# OBCv5_0.net
KiCad netlist of a schematic drawn in EAGLE
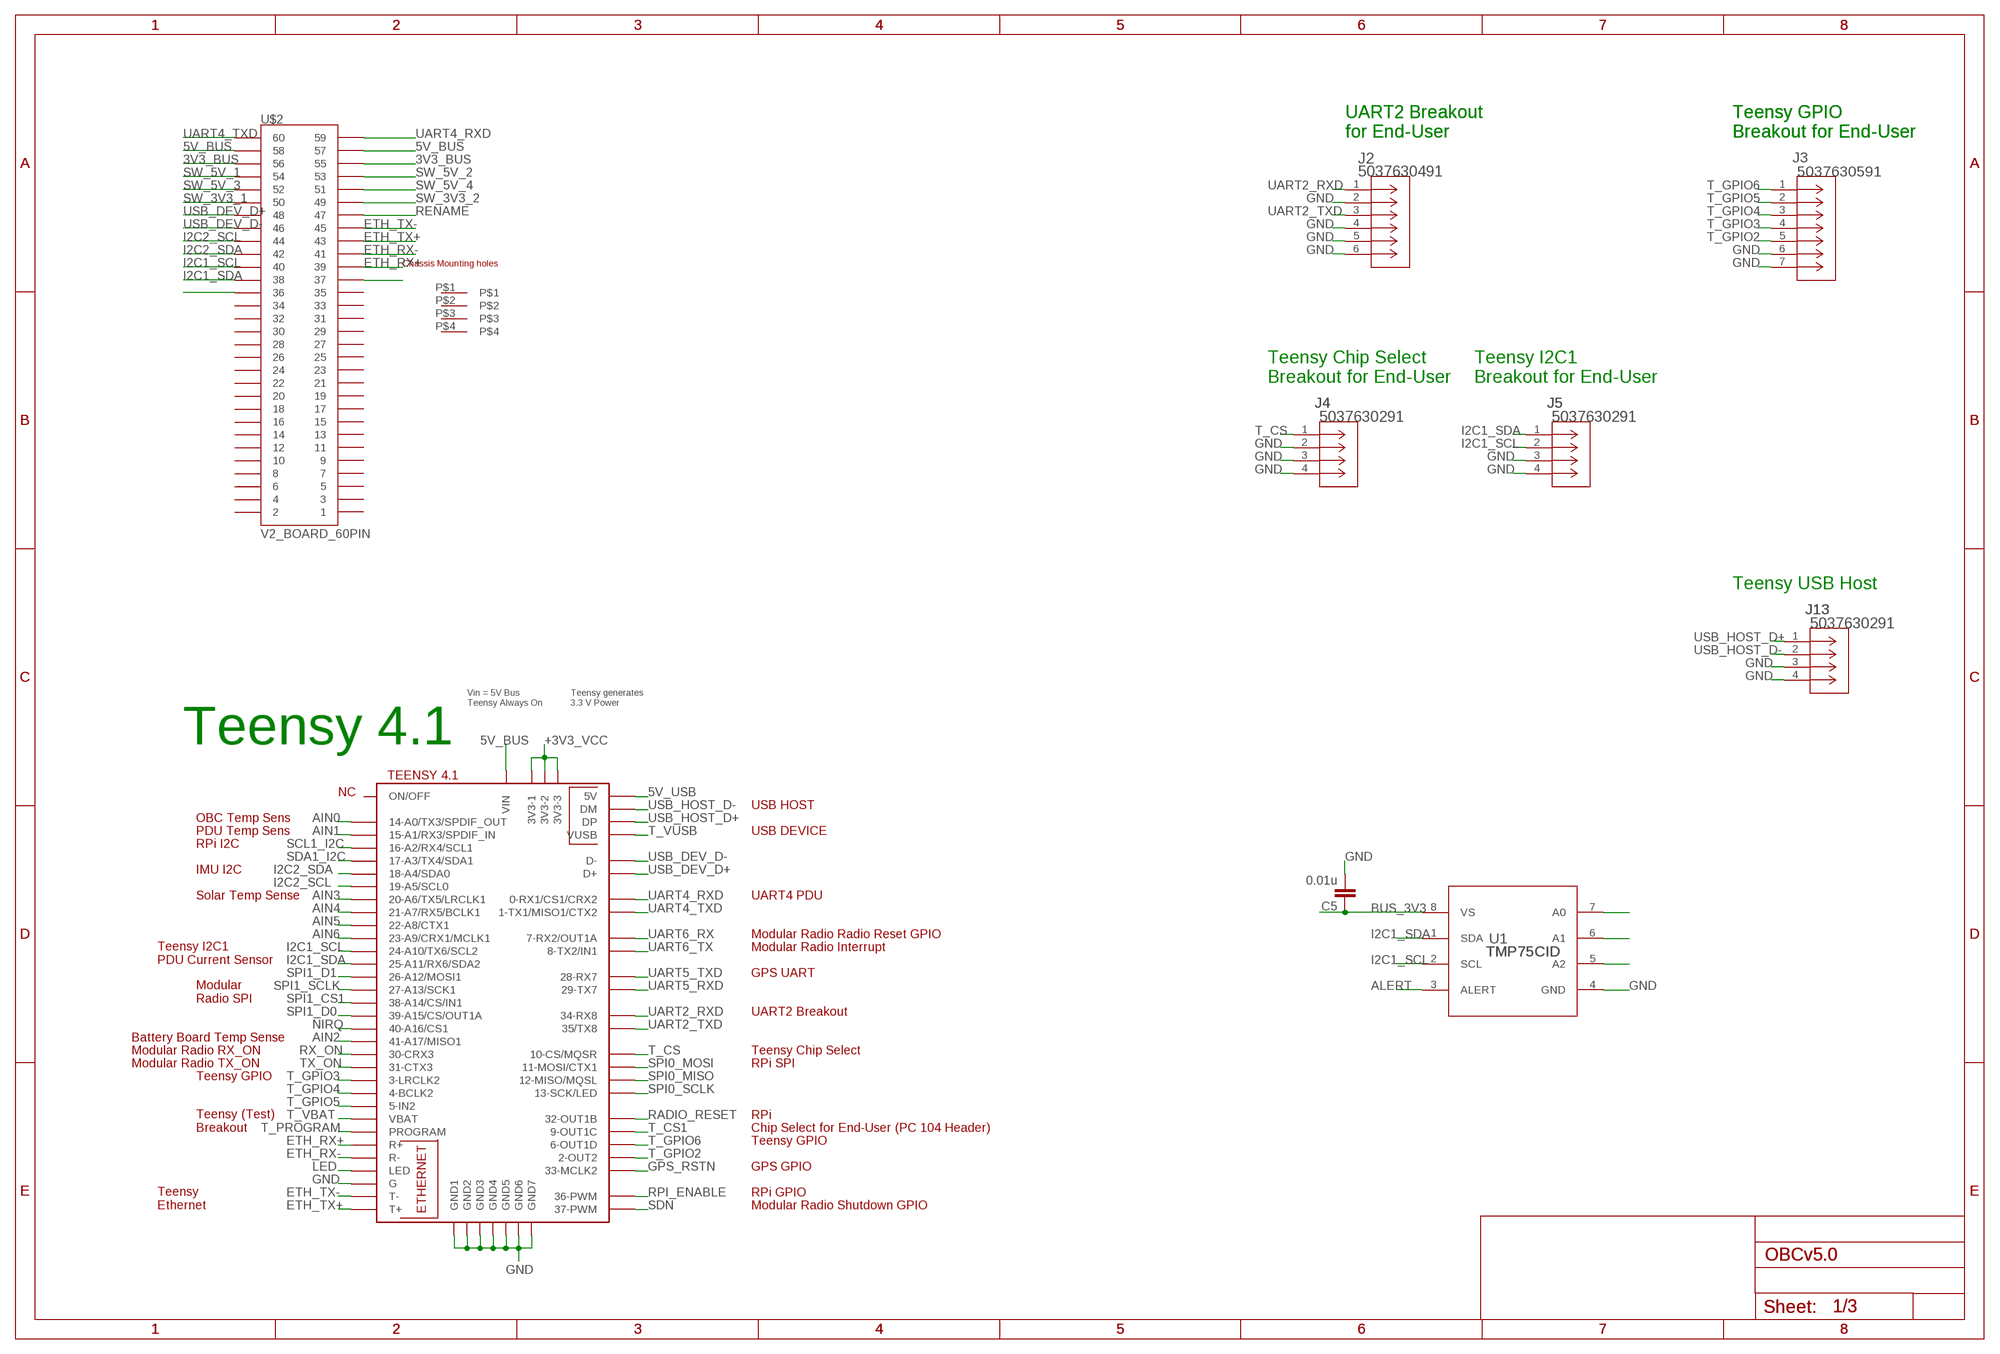
[diagram p0: schematic, sheet 1]
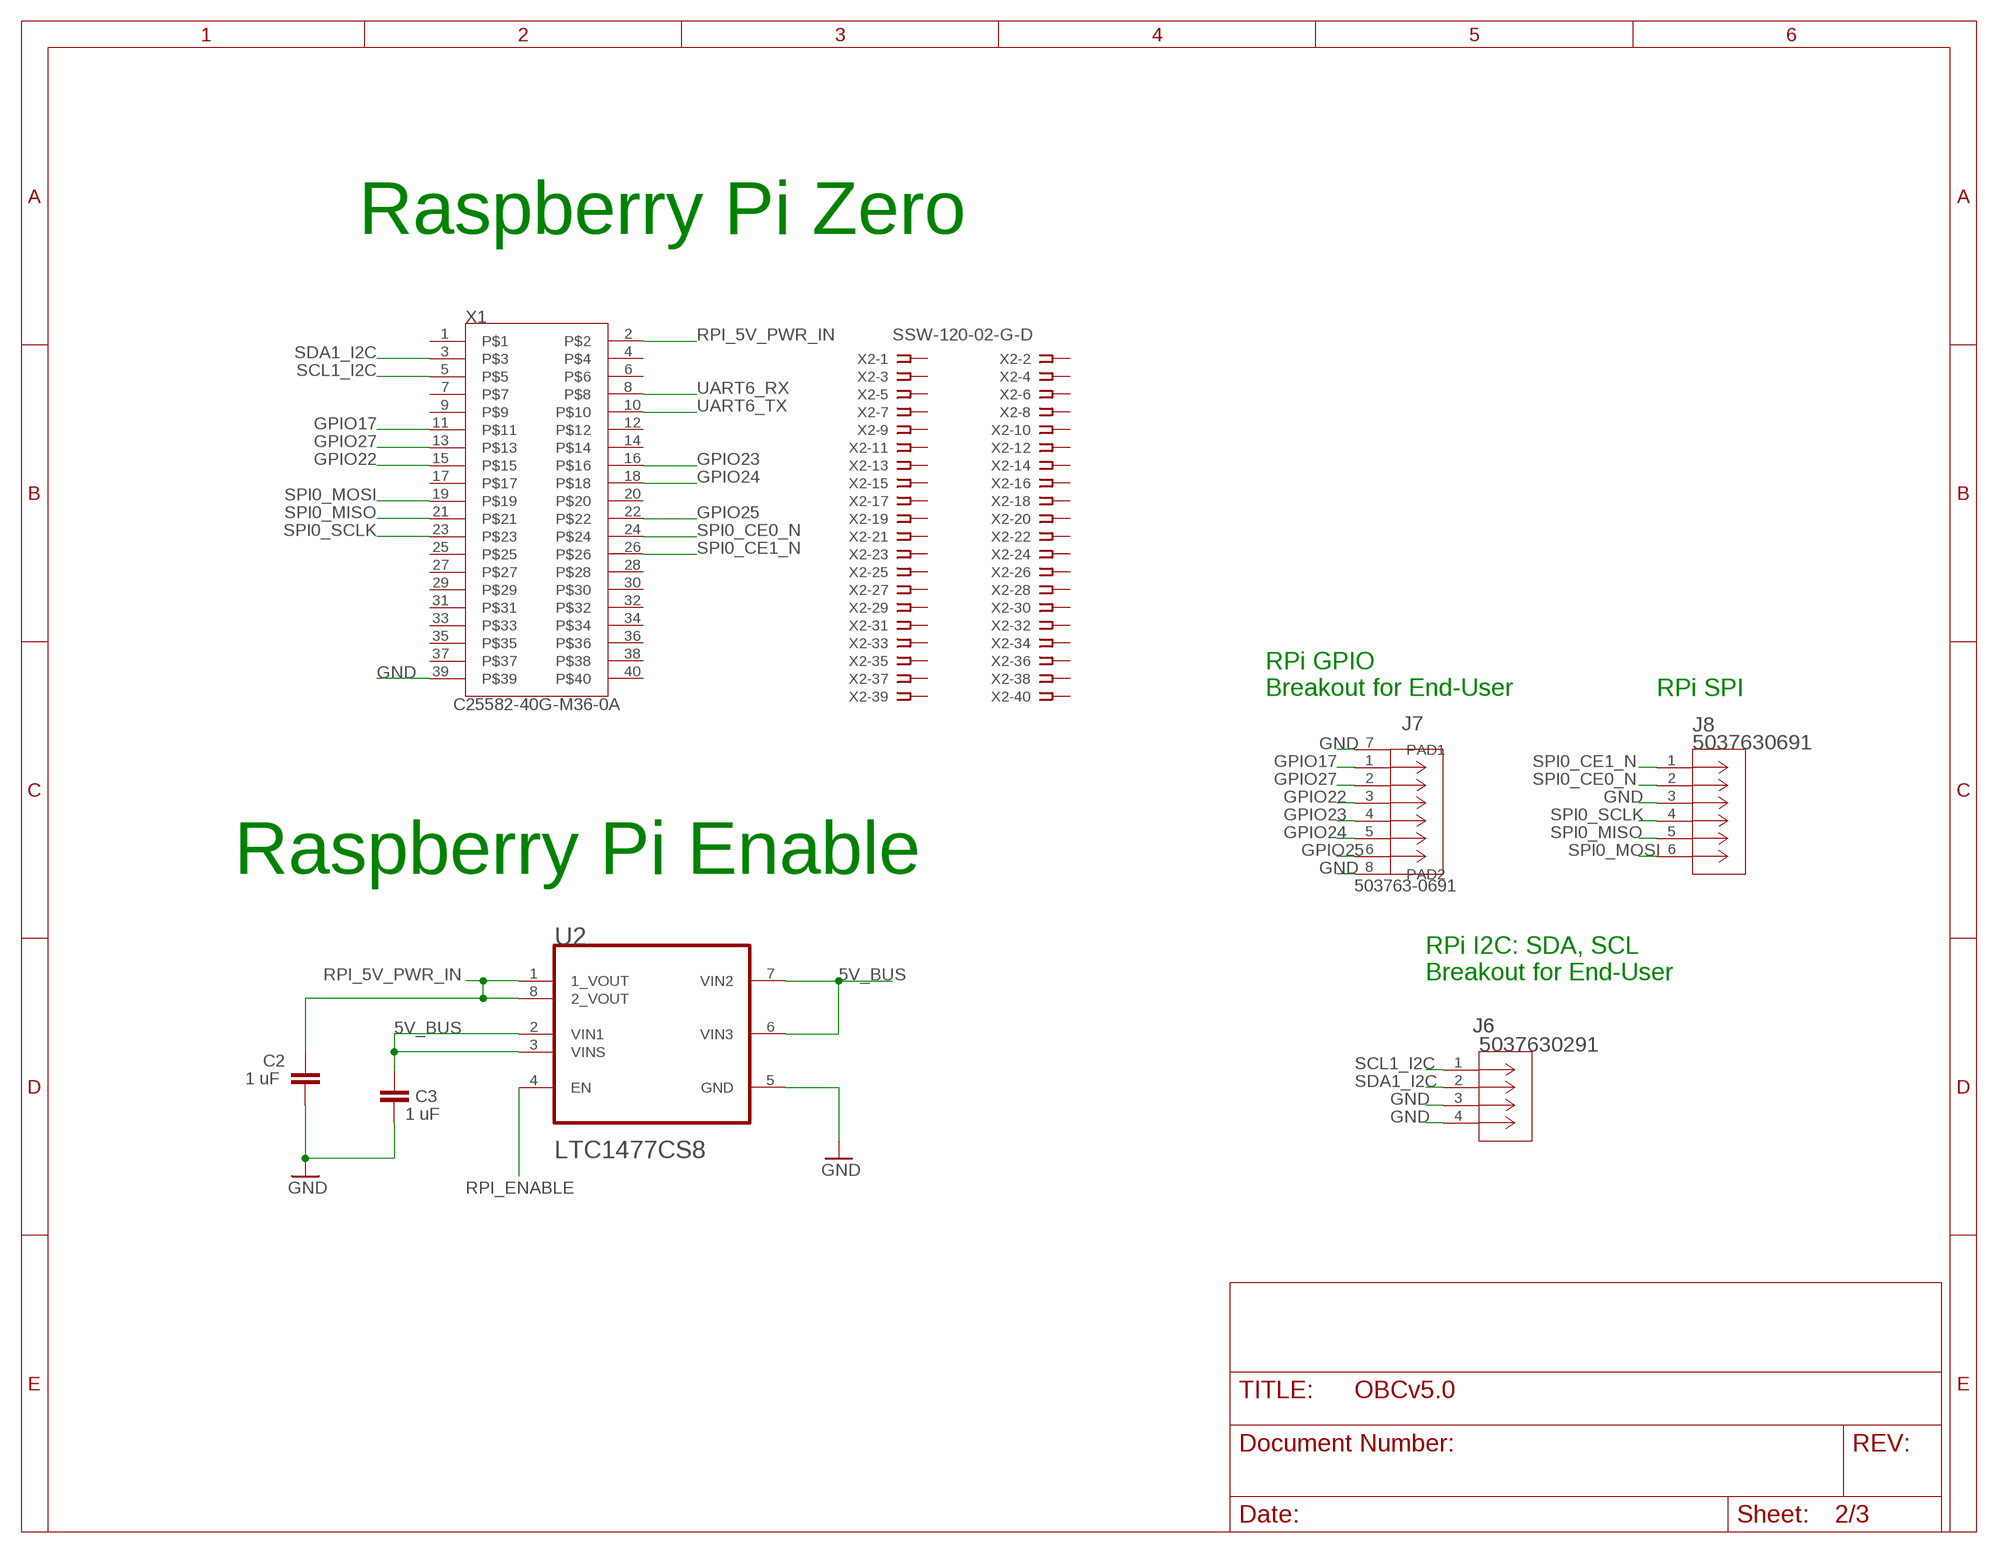
[diagram p1: schematic, sheet 2]
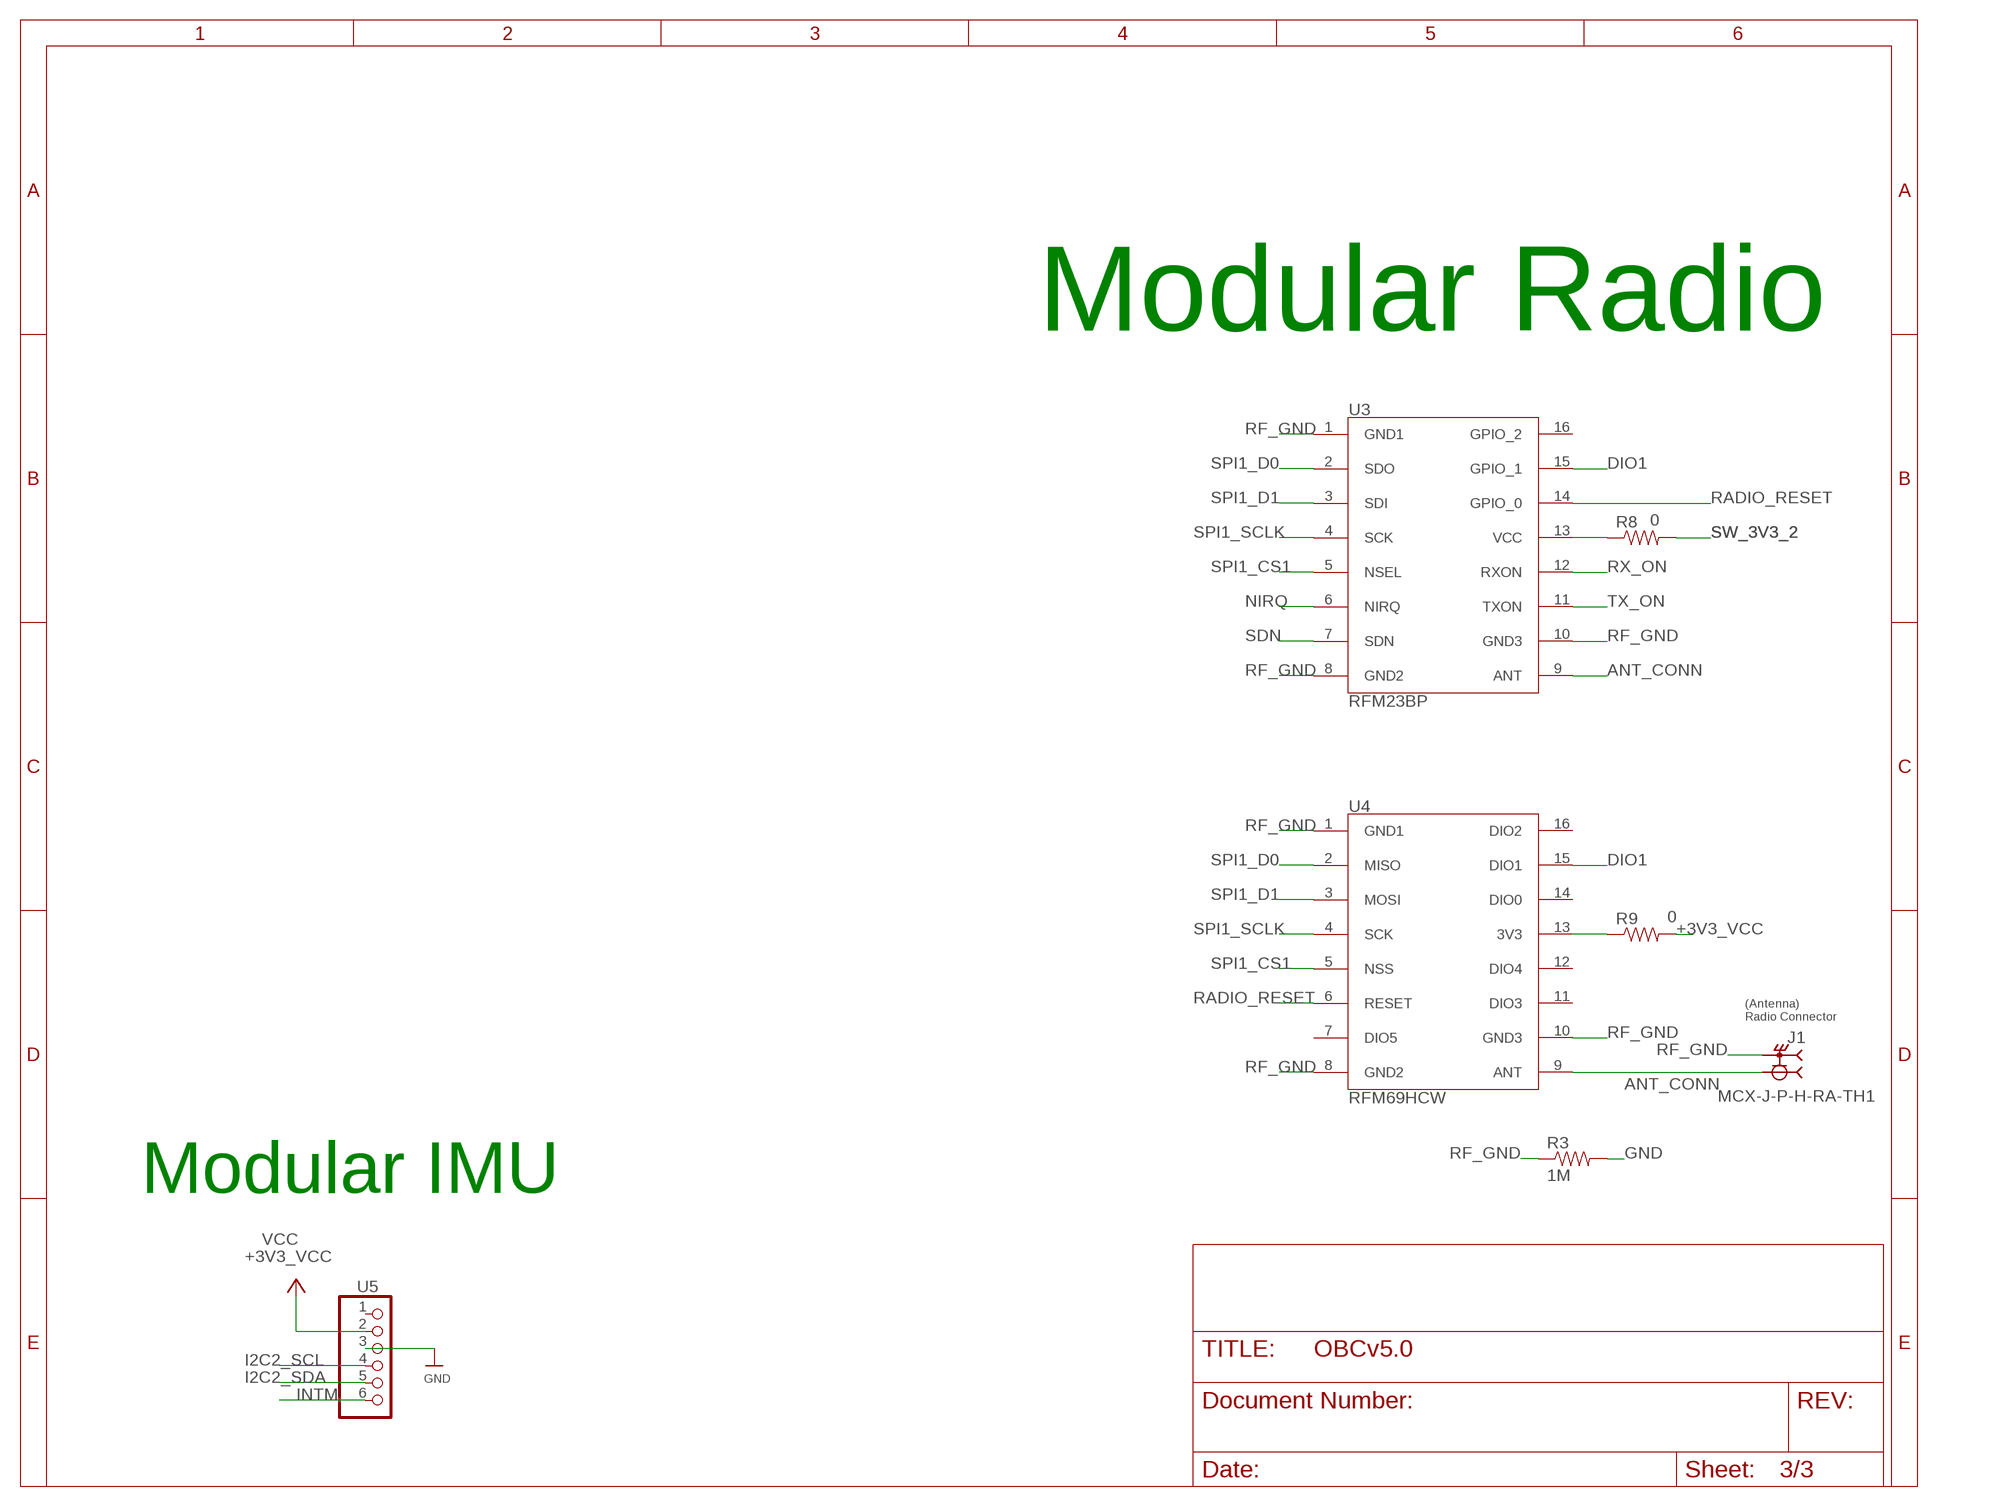
[diagram p2: schematic, sheet 3]

(export (version "E")
  (design (tool "Eeschema 10.0.6"))
  (components
    (comp (ref "C2")
      (value "1 uF")
      (footprint "eagle-import:0805")
      (libsource (lib "eagle-import") (part "CAP0805"))
    )
    (comp (ref "C3")
      (value "1 uF")
      (footprint "eagle-import:0805")
      (libsource (lib "eagle-import") (part "CAP0805"))
    )
    (comp (ref "J6")
      (value "5037630291")
      (footprint "eagle-import:CON_5037630291")
      (fields (field (name "COPYRIGHT") "Copyright (C) 2018 Accelerated Designs. All rights reserved"))
      (libsource (lib "eagle-import") (part "5037630291"))
    )
    (comp (ref "J7")
      (value "503763-0691")
      (footprint "eagle-import:CONN_503763-0691_MOL")
      (fields (field (name "COPYRIGHT") "Copyright (C) 2018 Accelerated Designs. All rights reserved"))
      (libsource (lib "eagle-import") (part "503763-0691"))
    )
    (comp (ref "J8")
      (value "5037630691")
      (footprint "eagle-import:CONN_503763-0691_MOL")
      (fields
        (field (name "MANUFACTURER_PART_NUMBER") "503763-0691")
        (field (name "COPYRIGHT") "Copyright (C) 2018 Accelerated Designs. All rights reserved")
      )
      (libsource (lib "eagle-import") (part "5037630691"))
    )
    (comp (ref "U2")
      (value "LTC1477CS8LINEAR_TECHNOLOGY_LTC1477CS8_0_2")
      (footprint "eagle-import:LINEAR_TECHNOLOGY_LTC1477CS8_2")
      (fields (field (name "MF") "Linear Technology") (field (name "MPN") "LTC1477CS8"))
      (libsource (lib "eagle-import") (part "LTC1477CS8LINEAR_TECHNOLOGY_LTC1477CS8_0_2"))
    )
    (comp (ref "X1")
      (value "C25582-40G-M36-0A")
      (footprint "eagle-import:ADAFRUIT_C25582-40G-M36-0A_0")
      (libsource (lib "eagle-import") (part "C25582-40G-M36-0A"))
    )
    (comp (ref "X2")
      (value "SSW-120-02-G-D")
      (footprint "eagle-import:SSW-120-02-G-D")
      (fields (field (name "MF") "Samtec Inc."))
      (libsource (lib "eagle-import") (part "SSW-120-02-G-D"))
    )
    (comp (ref "C5")
      (value "0.01u")
      (footprint "eagle-import:0805")
      (libsource (lib "eagle-import") (part "HSFL_Main_Library (1)_CAP0805"))
    )
    (comp (ref "J2")
      (value "5037630491")
      (footprint "eagle-import:CON_5037630491")
      (fields (field (name "COPYRIGHT") "Copyright (C) 2018 Accelerated Designs. All rights reserved"))
      (libsource (lib "eagle-import") (part "5037630491"))
    )
    (comp (ref "J3")
      (value "5037630591")
      (footprint "eagle-import:CON_5037630591")
      (fields (field (name "COPYRIGHT") "Copyright (C) 2021 Ultra Librarian. All rights reserved."))
      (libsource (lib "eagle-import") (part "5037630591"))
    )
    (comp (ref "J4")
      (value "5037630291")
      (footprint "eagle-import:CON_5037630291")
      (fields (field (name "COPYRIGHT") "Copyright (C) 2018 Accelerated Designs. All rights reserved"))
      (libsource (lib "eagle-import") (part "5037630291"))
    )
    (comp (ref "J5")
      (value "5037630291")
      (footprint "eagle-import:CON_5037630291")
      (fields (field (name "COPYRIGHT") "Copyright (C) 2018 Accelerated Designs. All rights reserved"))
      (libsource (lib "eagle-import") (part "5037630291"))
    )
    (comp (ref "J13")
      (value "5037630291")
      (footprint "eagle-import:CON_5037630291")
      (fields (field (name "COPYRIGHT") "Copyright (C) 2018 Accelerated Designs. All rights reserved"))
      (libsource (lib "eagle-import") (part "5037630291"))
    )
    (comp (ref "U$1")
      (value "TEENSY41TEENSY")
      (footprint "eagle-import:TEENSY41")
      (libsource (lib "eagle-import") (part "TEENSY41TEENSY"))
    )
    (comp (ref "U$2")
      (value "V2_BOARD_60PIN")
      (footprint "eagle-import:PC104_WCONN_BACKPLANE_HEADER")
      (libsource (lib "eagle-import") (part "V2_BOARD_60PIN"))
    )
    (comp (ref "U1")
      (value "TMP75CID")
      (footprint "eagle-import:D0008A_N")
      (fields (field (name "COPYRIGHT") "Copyright (C) 2023 Ultra Librarian. All rights reserved."))
      (libsource (lib "eagle-import") (part "TMP75CID"))
    )
    (comp (ref "J1")
      (value "MCX-J-P-H-RA-TH1")
      (footprint "eagle-import:SAMTEC_MCX-J-P-H-RA-TH1")
      (fields (field (name "DIGI-KEY_PART_NUMBER") "SAM10607-ND") (field (name "MF") "Samtec"))
      (libsource (lib "eagle-import") (part "MCX-J-P-H-RA-TH1"))
    )
    (comp (ref "R3")
      (value "1M")
      (footprint "eagle-import:0805")
      (libsource (lib "eagle-import") (part "RESISTOR0805-RES"))
    )
    (comp (ref "R8")
      (value "0")
      (footprint "eagle-import:R2512")
      (libsource (lib "eagle-import") (part "RESISTOR2512"))
    )
    (comp (ref "R9")
      (value "0")
      (footprint "eagle-import:R2512")
      (libsource (lib "eagle-import") (part "RESISTOR2512"))
    )
    (comp (ref "U3")
      (value "RFM23BP")
      (footprint "eagle-import:RFM23BP")
      (libsource (lib "eagle-import") (part "RFM23BP"))
    )
    (comp (ref "U4")
      (value "RFM69HCW")
      (footprint "eagle-import:RFM69HCW")
      (libsource (lib "eagle-import") (part "RFM69HCW"))
    )
    (comp (ref "U5")
      (value "HEADER-1X670MIL")
      (footprint "eagle-import:1X06_ROUND_70")
      (libsource (lib "eagle-import") (part "HEADER-1X670MIL"))
    )
  )
  (nets
    (net (code "1") (name "+3V3_VCC") (class "Default")
      (node (ref "R9") (pin "2") (pinfunction "2_2") (pintype "passive"))
      (node (ref "U$1") (pin "3V3-1") (pinfunction "3V3-1_3V3-1") (pintype "bidirectional"))
      (node (ref "U$1") (pin "3V3-2") (pinfunction "3V3-2_3V3-2") (pintype "bidirectional"))
      (node (ref "U$1") (pin "3V3-3") (pinfunction "3V3-3_3V3-3") (pintype "bidirectional"))
      (node (ref "U5") (pin "2") (pinfunction "2_2") (pintype "passive"))
    )
    (net (code "2") (name "3V3_BUS") (class "Default")
      (node (ref "U$2") (pin "55") (pinfunction "55_55") (pintype "bidirectional"))
      (node (ref "U$2") (pin "56") (pinfunction "56_56") (pintype "bidirectional"))
    )
    (net (code "3") (name "5V_BUS") (class "Default")
      (node (ref "C3") (pin "1") (pinfunction "1_1") (pintype "passive"))
      (node (ref "U$1") (pin "VIN") (pinfunction "VIN_VIN") (pintype "bidirectional"))
      (node (ref "U$2") (pin "57") (pinfunction "57_57") (pintype "bidirectional"))
      (node (ref "U$2") (pin "58") (pinfunction "58_58") (pintype "bidirectional"))
      (node (ref "U2") (pin "2") (pinfunction "VIN1_2") (pintype "power_in"))
      (node (ref "U2") (pin "3") (pinfunction "VINS_3") (pintype "power_in"))
      (node (ref "U2") (pin "6") (pinfunction "VIN3_6") (pintype "power_in"))
      (node (ref "U2") (pin "7") (pinfunction "VIN2_7") (pintype "power_in"))
    )
    (net (code "4") (name "5V_USB") (class "Default")
      (node (ref "U$1") (pin "+5V") (pinfunction "5V_+5V") (pintype "bidirectional"))
    )
    (net (code "5") (name "AIN0") (class "Default")
      (node (ref "U$1") (pin "14-A0/TX3/SPDIF_OUT") (pinfunction "14-A0/TX3/SPDIF_OUT_14-A0/TX3/SPDIF_OUT") (pintype "bidirectional"))
    )
    (net (code "6") (name "AIN1") (class "Default")
      (node (ref "U$1") (pin "15-A1/RX3/SPDIF_IN") (pinfunction "15-A1/RX3/SPDIF_IN_15-A1/RX3/SPDIF_IN") (pintype "bidirectional"))
    )
    (net (code "7") (name "AIN2") (class "Default")
      (node (ref "U$1") (pin "41-A17/MISO1") (pinfunction "41-A17/MISO1_41-A17/MISO1") (pintype "bidirectional"))
    )
    (net (code "8") (name "AIN3") (class "Default")
      (node (ref "U$1") (pin "20-A6/TX5/LRCLK1") (pinfunction "20-A6/TX5/LRCLK1_20-A6/TX5/LRCLK1") (pintype "bidirectional"))
    )
    (net (code "9") (name "AIN4") (class "Default")
      (node (ref "U$1") (pin "21-A7/RX5/BCLK1") (pinfunction "21-A7/RX5/BCLK1_21-A7/RX5/BCLK1") (pintype "bidirectional"))
    )
    (net (code "10") (name "AIN5") (class "Default")
      (node (ref "U$1") (pin "22-A8/CTX1") (pinfunction "22-A8/CTX1_22-A8/CTX1") (pintype "bidirectional"))
    )
    (net (code "11") (name "AIN6") (class "Default")
      (node (ref "U$1") (pin "23-A9/CRX1/MCLK1") (pinfunction "23-A9/CRX1/MCLK1_23-A9/CRX1/MCLK1") (pintype "bidirectional"))
    )
    (net (code "12") (name "ALERT") (class "Default")
      (node (ref "U1") (pin "3") (pinfunction "ALERT_3") (pintype "open_collector"))
    )
    (net (code "13") (name "ANT_CONN") (class "Default")
      (node (ref "J1") (pin "1") (pinfunction "1_1") (pintype "passive"))
      (node (ref "U3") (pin "9") (pinfunction "ANT_9") (pintype "bidirectional"))
      (node (ref "U4") (pin "9") (pinfunction "ANT_9") (pintype "bidirectional"))
    )
    (net (code "14") (name "BUS_3V3") (class "Default")
      (node (ref "C5") (pin "1") (pinfunction "1_1") (pintype "passive"))
      (node (ref "U1") (pin "8") (pinfunction "VS_8") (pintype "power_in"))
    )
    (net (code "15") (name "DIO1") (class "Default")
      (node (ref "U3") (pin "15") (pinfunction "GPIO_1_15") (pintype "bidirectional"))
      (node (ref "U4") (pin "15") (pinfunction "DIO1_15") (pintype "bidirectional"))
    )
    (net (code "16") (name "ETH_RX+") (class "Default")
      (node (ref "U$1") (pin "R+") (pinfunction "R+_R+") (pintype "bidirectional"))
      (node (ref "U$2") (pin "39") (pinfunction "39_39") (pintype "bidirectional"))
    )
    (net (code "17") (name "ETH_RX-") (class "Default")
      (node (ref "U$1") (pin "R-") (pinfunction "R-_R-") (pintype "bidirectional"))
      (node (ref "U$2") (pin "41") (pinfunction "41_41") (pintype "bidirectional"))
    )
    (net (code "18") (name "ETH_TX+") (class "Default")
      (node (ref "U$1") (pin "T+") (pinfunction "T+_T+") (pintype "bidirectional"))
      (node (ref "U$2") (pin "43") (pinfunction "43_43") (pintype "bidirectional"))
    )
    (net (code "19") (name "ETH_TX-") (class "Default")
      (node (ref "U$1") (pin "T-") (pinfunction "T-_T-") (pintype "bidirectional"))
      (node (ref "U$2") (pin "45") (pinfunction "45_45") (pintype "bidirectional"))
    )
    (net (code "20") (name "GND") (class "Default")
      (node (ref "C2") (pin "2") (pinfunction "2_2") (pintype "passive"))
      (node (ref "C3") (pin "2") (pinfunction "2_2") (pintype "passive"))
      (node (ref "C5") (pin "2") (pinfunction "2_2") (pintype "passive"))
      (node (ref "J13") (pin "3") (pinfunction "3_3") (pintype "passive"))
      (node (ref "J13") (pin "4") (pinfunction "4_4") (pintype "passive"))
      (node (ref "J2") (pin "2") (pinfunction "2_2") (pintype "passive"))
      (node (ref "J2") (pin "4") (pinfunction "4_4") (pintype "passive"))
      (node (ref "J2") (pin "5") (pinfunction "5_5") (pintype "passive"))
      (node (ref "J2") (pin "6") (pinfunction "6_6") (pintype "passive"))
      (node (ref "J3") (pin "6") (pinfunction "6_6") (pintype "passive"))
      (node (ref "J3") (pin "7") (pinfunction "7_7") (pintype "passive"))
      (node (ref "J4") (pin "2") (pinfunction "2_2") (pintype "passive"))
      (node (ref "J4") (pin "3") (pinfunction "3_3") (pintype "passive"))
      (node (ref "J4") (pin "4") (pinfunction "4_4") (pintype "passive"))
      (node (ref "J5") (pin "3") (pinfunction "3_3") (pintype "passive"))
      (node (ref "J5") (pin "4") (pinfunction "4_4") (pintype "passive"))
      (node (ref "J6") (pin "3") (pinfunction "3_3") (pintype "passive"))
      (node (ref "J6") (pin "4") (pinfunction "4_4") (pintype "passive"))
      (node (ref "J7") (pin "7") (pinfunction "PAD1_7") (pintype "bidirectional"))
      (node (ref "J7") (pin "8") (pinfunction "PAD2_8") (pintype "bidirectional"))
      (node (ref "J8") (pin "3") (pinfunction "3_3") (pintype "passive"))
      (node (ref "R3") (pin "2") (pinfunction "2_2") (pintype "passive"))
      (node (ref "U$1") (pin "G") (pinfunction "G_G") (pintype "bidirectional"))
      (node (ref "U$1") (pin "GND") (pinfunction "GND7_GND") (pintype "bidirectional"))
      (node (ref "U$1") (pin "GND1") (pinfunction "GND1_GND1") (pintype "bidirectional"))
      (node (ref "U$1") (pin "GND2") (pinfunction "GND2_GND2") (pintype "bidirectional"))
      (node (ref "U$1") (pin "GND3") (pinfunction "GND3_GND3") (pintype "bidirectional"))
      (node (ref "U$1") (pin "GND4") (pinfunction "GND4_GND4") (pintype "bidirectional"))
      (node (ref "U$1") (pin "GND5") (pinfunction "GND5_GND5") (pintype "bidirectional"))
      (node (ref "U$1") (pin "GND6") (pinfunction "GND6_GND6") (pintype "bidirectional"))
      (node (ref "U1") (pin "4") (pinfunction "GND_4") (pintype "power_in"))
      (node (ref "U2") (pin "5") (pinfunction "GND_5") (pintype "power_in"))
      (node (ref "U5") (pin "3") (pinfunction "3_3") (pintype "passive"))
      (node (ref "X1") (pin "39") (pinfunction "P$39_39") (pintype "bidirectional"))
    )
    (net (code "21") (name "GPIO17") (class "Default")
      (node (ref "J7") (pin "1") (pinfunction "1_1") (pintype "passive"))
      (node (ref "X1") (pin "11") (pinfunction "P$11_11") (pintype "bidirectional"))
    )
    (net (code "22") (name "GPIO22") (class "Default")
      (node (ref "J7") (pin "3") (pinfunction "3_3") (pintype "passive"))
      (node (ref "X1") (pin "15") (pinfunction "P$15_15") (pintype "bidirectional"))
    )
    (net (code "23") (name "GPIO23") (class "Default")
      (node (ref "J7") (pin "4") (pinfunction "4_4") (pintype "passive"))
      (node (ref "X1") (pin "16") (pinfunction "P$16_16") (pintype "bidirectional"))
    )
    (net (code "24") (name "GPIO24") (class "Default")
      (node (ref "J7") (pin "5") (pinfunction "5_5") (pintype "passive"))
      (node (ref "X1") (pin "18") (pinfunction "P$18_18") (pintype "bidirectional"))
    )
    (net (code "25") (name "GPIO25") (class "Default")
      (node (ref "J7") (pin "6") (pinfunction "6_6") (pintype "passive"))
      (node (ref "X1") (pin "22") (pinfunction "P$22_22") (pintype "bidirectional"))
    )
    (net (code "26") (name "GPIO27") (class "Default")
      (node (ref "J7") (pin "2") (pinfunction "2_2") (pintype "passive"))
      (node (ref "X1") (pin "13") (pinfunction "P$13_13") (pintype "bidirectional"))
    )
    (net (code "27") (name "GPS_RSTN") (class "Default")
      (node (ref "U$1") (pin "33-MCLK2") (pinfunction "33-MCLK2_33-MCLK2") (pintype "bidirectional"))
    )
    (net (code "28") (name "I2C1_SCL") (class "Default")
      (node (ref "J5") (pin "2") (pinfunction "2_2") (pintype "passive"))
      (node (ref "U$1") (pin "24-A10/TX6/SCL2") (pinfunction "24-A10/TX6/SCL2_24-A10/TX6/SCL2") (pintype "bidirectional"))
      (node (ref "U$2") (pin "40") (pinfunction "40_40") (pintype "bidirectional"))
      (node (ref "U1") (pin "2") (pinfunction "SCL_2") (pintype "input"))
    )
    (net (code "29") (name "I2C1_SDA") (class "Default")
      (node (ref "J5") (pin "1") (pinfunction "1_1") (pintype "passive"))
      (node (ref "U$1") (pin "25-A11/RX6/SDA2") (pinfunction "25-A11/RX6/SDA2_25-A11/RX6/SDA2") (pintype "bidirectional"))
      (node (ref "U$2") (pin "38") (pinfunction "38_38") (pintype "bidirectional"))
      (node (ref "U1") (pin "1") (pinfunction "SDA_1") (pintype "bidirectional"))
    )
    (net (code "30") (name "I2C2_SCL") (class "Default")
      (node (ref "U$1") (pin "19-A5/SCL0") (pinfunction "19-A5/SCL0_19-A5/SCL0") (pintype "bidirectional"))
      (node (ref "U$2") (pin "44") (pinfunction "44_44") (pintype "bidirectional"))
      (node (ref "U5") (pin "4") (pinfunction "4_4") (pintype "passive"))
    )
    (net (code "31") (name "I2C2_SDA") (class "Default")
      (node (ref "U$1") (pin "18-A4/SDA0") (pinfunction "18-A4/SDA0_18-A4/SDA0") (pintype "bidirectional"))
      (node (ref "U$2") (pin "42") (pinfunction "42_42") (pintype "bidirectional"))
      (node (ref "U5") (pin "5") (pinfunction "5_5") (pintype "passive"))
    )
    (net (code "32") (name "INTM") (class "Default")
      (node (ref "U5") (pin "6") (pinfunction "6_6") (pintype "passive"))
    )
    (net (code "33") (name "LED") (class "Default")
      (node (ref "U$1") (pin "LED") (pinfunction "LED_LED") (pintype "bidirectional"))
    )
    (net (code "34") (name "NIRQ") (class "Default")
      (node (ref "U$1") (pin "40-A16/CS1") (pinfunction "40-A16/CS1_40-A16/CS1") (pintype "bidirectional"))
      (node (ref "U3") (pin "6") (pinfunction "NIRQ_6") (pintype "bidirectional"))
    )
    (net (code "35") (name "Net-(U3-VCC)") (class "Default")
      (node (ref "R8") (pin "1") (pinfunction "1_1") (pintype "passive"))
      (node (ref "U3") (pin "13") (pinfunction "VCC_13") (pintype "bidirectional"))
    )
    (net (code "36") (name "Net-(U4-3V3)") (class "Default")
      (node (ref "R9") (pin "1") (pinfunction "1_1") (pintype "passive"))
      (node (ref "U4") (pin "13") (pinfunction "3V3_13") (pintype "bidirectional"))
    )
    (net (code "37") (name "RADIO_RESET") (class "Default")
      (node (ref "U$1") (pin "32-OUT1B") (pinfunction "32-OUT1B_32-OUT1B") (pintype "bidirectional"))
      (node (ref "U3") (pin "14") (pinfunction "GPIO_0_14") (pintype "bidirectional"))
      (node (ref "U4") (pin "6") (pinfunction "RESET_6") (pintype "bidirectional"))
    )
    (net (code "38") (name "RENAME") (class "Default")
      (node (ref "U$2") (pin "47") (pinfunction "47_47") (pintype "bidirectional"))
    )
    (net (code "39") (name "RF_GND") (class "Default")
      (node (ref "J1") (pin "S1") (pinfunction "2_S1") (pintype "passive"))
      (node (ref "J1") (pin "S2") (pinfunction "2_S2") (pintype "passive"))
      (node (ref "J1") (pin "S3") (pinfunction "2_S3") (pintype "passive"))
      (node (ref "J1") (pin "S4") (pinfunction "2_S4") (pintype "passive"))
      (node (ref "R3") (pin "1") (pinfunction "1_1") (pintype "passive"))
      (node (ref "U3") (pin "1") (pinfunction "GND1_1") (pintype "bidirectional"))
      (node (ref "U3") (pin "10") (pinfunction "GND3_10") (pintype "bidirectional"))
      (node (ref "U3") (pin "8") (pinfunction "GND2_8") (pintype "bidirectional"))
      (node (ref "U4") (pin "1") (pinfunction "GND1_1") (pintype "bidirectional"))
      (node (ref "U4") (pin "10") (pinfunction "GND3_10") (pintype "bidirectional"))
      (node (ref "U4") (pin "8") (pinfunction "GND2_8") (pintype "bidirectional"))
    )
    (net (code "40") (name "RPI_5V_PWR_IN") (class "Default")
      (node (ref "C2") (pin "1") (pinfunction "1_1") (pintype "passive"))
      (node (ref "U2") (pin "1") (pinfunction "1_VOUT_1") (pintype "power_in"))
      (node (ref "U2") (pin "8") (pinfunction "2_VOUT_8") (pintype "power_in"))
      (node (ref "X1") (pin "2") (pinfunction "P$2_2") (pintype "bidirectional"))
    )
    (net (code "41") (name "RPI_ENABLE") (class "Default")
      (node (ref "U$1") (pin "36-PWM") (pinfunction "36-PWM_36-PWM") (pintype "bidirectional"))
      (node (ref "U2") (pin "4") (pinfunction "EN_4") (pintype "input"))
    )
    (net (code "42") (name "RX_ON") (class "Default")
      (node (ref "U$1") (pin "30-CRX3") (pinfunction "30-CRX3_30-CRX3") (pintype "bidirectional"))
      (node (ref "U3") (pin "12") (pinfunction "RXON_12") (pintype "bidirectional"))
    )
    (net (code "43") (name "SCL1_I2C") (class "Default")
      (node (ref "J6") (pin "1") (pinfunction "1_1") (pintype "passive"))
      (node (ref "U$1") (pin "16-A2/RX4/SCL1") (pinfunction "16-A2/RX4/SCL1_16-A2/RX4/SCL1") (pintype "bidirectional"))
      (node (ref "X1") (pin "5") (pinfunction "P$5_5") (pintype "bidirectional"))
    )
    (net (code "44") (name "SDA1_I2C") (class "Default")
      (node (ref "J6") (pin "2") (pinfunction "2_2") (pintype "passive"))
      (node (ref "U$1") (pin "17-A3/TX4/SDA1") (pinfunction "17-A3/TX4/SDA1_17-A3/TX4/SDA1") (pintype "bidirectional"))
      (node (ref "X1") (pin "3") (pinfunction "P$3_3") (pintype "bidirectional"))
    )
    (net (code "45") (name "SDN") (class "Default")
      (node (ref "U$1") (pin "37-PWM") (pinfunction "37-PWM_37-PWM") (pintype "bidirectional"))
      (node (ref "U3") (pin "7") (pinfunction "SDN_7") (pintype "bidirectional"))
    )
    (net (code "46") (name "SPI0_CE0_N") (class "Default")
      (node (ref "J8") (pin "2") (pinfunction "2_2") (pintype "passive"))
      (node (ref "X1") (pin "24") (pinfunction "P$24_24") (pintype "bidirectional"))
    )
    (net (code "47") (name "SPI0_CE1_N") (class "Default")
      (node (ref "J8") (pin "1") (pinfunction "1_1") (pintype "passive"))
      (node (ref "X1") (pin "26") (pinfunction "P$26_26") (pintype "bidirectional"))
    )
    (net (code "48") (name "SPI0_MISO") (class "Default")
      (node (ref "J8") (pin "5") (pinfunction "5_5") (pintype "passive"))
      (node (ref "U$1") (pin "12-MISO/MQSL") (pinfunction "12-MISO/MQSL_12-MISO/MQSL") (pintype "bidirectional"))
      (node (ref "X1") (pin "21") (pinfunction "P$21_21") (pintype "bidirectional"))
    )
    (net (code "49") (name "SPI0_MOSI") (class "Default")
      (node (ref "J8") (pin "6") (pinfunction "6_6") (pintype "passive"))
      (node (ref "U$1") (pin "11-MOSI/CTX1") (pinfunction "11-MOSI/CTX1_11-MOSI/CTX1") (pintype "bidirectional"))
      (node (ref "X1") (pin "19") (pinfunction "P$19_19") (pintype "bidirectional"))
    )
    (net (code "50") (name "SPI0_SCLK") (class "Default")
      (node (ref "J8") (pin "4") (pinfunction "4_4") (pintype "passive"))
      (node (ref "U$1") (pin "13-SCK/LED") (pinfunction "13-SCK/LED_13-SCK/LED") (pintype "bidirectional"))
      (node (ref "X1") (pin "23") (pinfunction "P$23_23") (pintype "bidirectional"))
    )
    (net (code "51") (name "SPI1_CS1") (class "Default")
      (node (ref "U$1") (pin "38-A14/CS/IN1") (pinfunction "38-A14/CS/IN1_38-A14/CS/IN1") (pintype "bidirectional"))
      (node (ref "U3") (pin "5") (pinfunction "NSEL_5") (pintype "bidirectional"))
      (node (ref "U4") (pin "5") (pinfunction "NSS_5") (pintype "bidirectional"))
    )
    (net (code "52") (name "SPI1_D0") (class "Default")
      (node (ref "U$1") (pin "39-A15/CS/OUT1A") (pinfunction "39-A15/CS/OUT1A_39-A15/CS/OUT1A") (pintype "bidirectional"))
      (node (ref "U3") (pin "2") (pinfunction "SDO_2") (pintype "bidirectional"))
      (node (ref "U4") (pin "2") (pinfunction "MISO_2") (pintype "bidirectional"))
    )
    (net (code "53") (name "SPI1_D1") (class "Default")
      (node (ref "U$1") (pin "26-A12/MOSI1") (pinfunction "26-A12/MOSI1_26-A12/MOSI1") (pintype "bidirectional"))
      (node (ref "U3") (pin "3") (pinfunction "SDI_3") (pintype "bidirectional"))
      (node (ref "U4") (pin "3") (pinfunction "MOSI_3") (pintype "bidirectional"))
    )
    (net (code "54") (name "SPI1_SCLK") (class "Default")
      (node (ref "U$1") (pin "27-A13/SCK1") (pinfunction "27-A13/SCK1_27-A13/SCK1") (pintype "bidirectional"))
      (node (ref "U3") (pin "4") (pinfunction "SCK_4") (pintype "bidirectional"))
      (node (ref "U4") (pin "4") (pinfunction "SCK_4") (pintype "bidirectional"))
    )
    (net (code "55") (name "SW_3V3_1") (class "Default")
      (node (ref "U$2") (pin "50") (pinfunction "50_50") (pintype "bidirectional"))
    )
    (net (code "56") (name "SW_3V3_2") (class "Default")
      (node (ref "R8") (pin "2") (pinfunction "2_2") (pintype "passive"))
      (node (ref "U$2") (pin "49") (pinfunction "49_49") (pintype "bidirectional"))
    )
    (net (code "57") (name "SW_5V_1") (class "Default")
      (node (ref "U$2") (pin "54") (pinfunction "54_54") (pintype "bidirectional"))
    )
    (net (code "58") (name "SW_5V_2") (class "Default")
      (node (ref "U$2") (pin "53") (pinfunction "53_53") (pintype "bidirectional"))
    )
    (net (code "59") (name "SW_5V_3") (class "Default")
      (node (ref "U$2") (pin "52") (pinfunction "52_52") (pintype "bidirectional"))
    )
    (net (code "60") (name "SW_5V_4") (class "Default")
      (node (ref "U$2") (pin "51") (pinfunction "51_51") (pintype "bidirectional"))
    )
    (net (code "61") (name "TX_ON") (class "Default")
      (node (ref "U$1") (pin "31-CTX3") (pinfunction "31-CTX3_31-CTX3") (pintype "bidirectional"))
      (node (ref "U3") (pin "11") (pinfunction "TXON_11") (pintype "bidirectional"))
    )
    (net (code "62") (name "T_CS") (class "Default")
      (node (ref "J4") (pin "1") (pinfunction "1_1") (pintype "passive"))
      (node (ref "U$1") (pin "10-CS\\MQSR") (pinfunction "10-CS/MQSR_10-CS\\MQSR") (pintype "bidirectional"))
    )
    (net (code "63") (name "T_CS1") (class "Default")
      (node (ref "U$1") (pin "9-OUT1C") (pinfunction "9-OUT1C_9-OUT1C") (pintype "bidirectional"))
    )
    (net (code "64") (name "T_GPIO2") (class "Default")
      (node (ref "J3") (pin "5") (pinfunction "5_5") (pintype "passive"))
      (node (ref "U$1") (pin "2-OUT2") (pinfunction "2-OUT2_2-OUT2") (pintype "bidirectional"))
    )
    (net (code "65") (name "T_GPIO3") (class "Default")
      (node (ref "J3") (pin "4") (pinfunction "4_4") (pintype "passive"))
      (node (ref "U$1") (pin "3-LRCLK2") (pinfunction "3-LRCLK2_3-LRCLK2") (pintype "bidirectional"))
    )
    (net (code "66") (name "T_GPIO4") (class "Default")
      (node (ref "J3") (pin "3") (pinfunction "3_3") (pintype "passive"))
      (node (ref "U$1") (pin "4-BCLK2") (pinfunction "4-BCLK2_4-BCLK2") (pintype "bidirectional"))
    )
    (net (code "67") (name "T_GPIO5") (class "Default")
      (node (ref "J3") (pin "2") (pinfunction "2_2") (pintype "passive"))
      (node (ref "U$1") (pin "5-IN2") (pinfunction "5-IN2_5-IN2") (pintype "bidirectional"))
    )
    (net (code "68") (name "T_GPIO6") (class "Default")
      (node (ref "J3") (pin "1") (pinfunction "1_1") (pintype "passive"))
      (node (ref "U$1") (pin "6-OUT1D") (pinfunction "6-OUT1D_6-OUT1D") (pintype "bidirectional"))
    )
    (net (code "69") (name "T_PROGRAM") (class "Default")
      (node (ref "U$1") (pin "PROGRAM") (pinfunction "PROGRAM_PROGRAM") (pintype "bidirectional"))
    )
    (net (code "70") (name "T_VBAT") (class "Default")
      (node (ref "U$1") (pin "VBAT") (pinfunction "VBAT_VBAT") (pintype "bidirectional"))
    )
    (net (code "71") (name "T_VUSB") (class "Default")
      (node (ref "U$1") (pin "VUSB") (pinfunction "VUSB_VUSB") (pintype "bidirectional"))
    )
    (net (code "72") (name "UART2_RXD") (class "Default")
      (node (ref "J2") (pin "1") (pinfunction "1_1") (pintype "passive"))
      (node (ref "U$1") (pin "34-RX8") (pinfunction "34-RX8_34-RX8") (pintype "bidirectional"))
    )
    (net (code "73") (name "UART2_TXD") (class "Default")
      (node (ref "J2") (pin "3") (pinfunction "3_3") (pintype "passive"))
      (node (ref "U$1") (pin "35-TX8") (pinfunction "35/TX8_35-TX8") (pintype "bidirectional"))
    )
    (net (code "74") (name "UART4_RXD") (class "Default")
      (node (ref "U$1") (pin "0-RX1/CS1/CRX2") (pinfunction "0-RX1/CS1/CRX2_0-RX1/CS1/CRX2") (pintype "bidirectional"))
      (node (ref "U$2") (pin "59") (pinfunction "59_59") (pintype "bidirectional"))
    )
    (net (code "75") (name "UART4_TXD") (class "Default")
      (node (ref "U$1") (pin "1-TX1/MISO1/CTX2") (pinfunction "1-TX1/MISO1/CTX2_1-TX1/MISO1/CTX2") (pintype "bidirectional"))
      (node (ref "U$2") (pin "60") (pinfunction "60_60") (pintype "bidirectional"))
    )
    (net (code "76") (name "UART5_RXD") (class "Default")
      (node (ref "U$1") (pin "29-TX7") (pinfunction "29-TX7_29-TX7") (pintype "bidirectional"))
    )
    (net (code "77") (name "UART5_TXD") (class "Default")
      (node (ref "U$1") (pin "28-RX7") (pinfunction "28-RX7_28-RX7") (pintype "bidirectional"))
    )
    (net (code "78") (name "UART6_RX") (class "Default")
      (node (ref "U$1") (pin "7-RX2/OUT1A") (pinfunction "7-RX2/OUT1A_7-RX2/OUT1A") (pintype "bidirectional"))
      (node (ref "X1") (pin "8") (pinfunction "P$8_8") (pintype "bidirectional"))
    )
    (net (code "79") (name "UART6_TX") (class "Default")
      (node (ref "U$1") (pin "8-TX2/IN1") (pinfunction "8-TX2/IN1_8-TX2/IN1") (pintype "bidirectional"))
      (node (ref "X1") (pin "10") (pinfunction "P$10_10") (pintype "bidirectional"))
    )
    (net (code "80") (name "USB_DEV_D+") (class "Default")
      (node (ref "U$1") (pin "D+") (pinfunction "D+_D+") (pintype "bidirectional"))
      (node (ref "U$2") (pin "48") (pinfunction "48_48") (pintype "bidirectional"))
    )
    (net (code "81") (name "USB_DEV_D-") (class "Default")
      (node (ref "U$1") (pin "D-") (pinfunction "D-_D-") (pintype "bidirectional"))
      (node (ref "U$2") (pin "46") (pinfunction "46_46") (pintype "bidirectional"))
    )
    (net (code "82") (name "USB_HOST_D+") (class "Default")
      (node (ref "J13") (pin "1") (pinfunction "1_1") (pintype "passive"))
      (node (ref "U$1") (pin "DP") (pinfunction "DP_DP") (pintype "bidirectional"))
    )
    (net (code "83") (name "USB_HOST_D-") (class "Default")
      (node (ref "J13") (pin "2") (pinfunction "2_2") (pintype "passive"))
      (node (ref "U$1") (pin "DM") (pinfunction "DM_DM") (pintype "bidirectional"))
    )
    (net (code "84") (name "unconnected-(U$1-PadON{slash}OFF)") (class "Default")
      (node (ref "U$1") (pin "ON/OFF") (pinfunction "ON/OFF_ON/OFF") (pintype "bidirectional"))
    )
    (net (code "85") (name "unconnected-(U$2-Pad1)") (class "Default")
      (node (ref "U$2") (pin "1") (pinfunction "1_1") (pintype "bidirectional"))
    )
    (net (code "86") (name "unconnected-(U$2-Pad2)") (class "Default")
      (node (ref "U$2") (pin "2") (pinfunction "2_2") (pintype "bidirectional"))
    )
    (net (code "87") (name "unconnected-(U$2-Pad3)") (class "Default")
      (node (ref "U$2") (pin "3") (pinfunction "3_3") (pintype "bidirectional"))
    )
    (net (code "88") (name "unconnected-(U$2-Pad4)") (class "Default")
      (node (ref "U$2") (pin "4") (pinfunction "4_4") (pintype "bidirectional"))
    )
    (net (code "89") (name "unconnected-(U$2-Pad5)") (class "Default")
      (node (ref "U$2") (pin "5") (pinfunction "5_5") (pintype "bidirectional"))
    )
    (net (code "90") (name "unconnected-(U$2-Pad6)") (class "Default")
      (node (ref "U$2") (pin "6") (pinfunction "6_6") (pintype "bidirectional"))
    )
    (net (code "91") (name "unconnected-(U$2-Pad7)") (class "Default")
      (node (ref "U$2") (pin "7") (pinfunction "7_7") (pintype "bidirectional"))
    )
    (net (code "92") (name "unconnected-(U$2-Pad8)") (class "Default")
      (node (ref "U$2") (pin "8") (pinfunction "8_8") (pintype "bidirectional"))
    )
    (net (code "93") (name "unconnected-(U$2-Pad9)") (class "Default")
      (node (ref "U$2") (pin "9") (pinfunction "9_9") (pintype "bidirectional"))
    )
    (net (code "94") (name "unconnected-(U$2-Pad10)") (class "Default")
      (node (ref "U$2") (pin "10") (pinfunction "10_10") (pintype "bidirectional"))
    )
    (net (code "95") (name "unconnected-(U$2-Pad11)") (class "Default")
      (node (ref "U$2") (pin "11") (pinfunction "11_11") (pintype "bidirectional"))
    )
    (net (code "96") (name "unconnected-(U$2-Pad12)") (class "Default")
      (node (ref "U$2") (pin "12") (pinfunction "12_12") (pintype "bidirectional"))
    )
    (net (code "97") (name "unconnected-(U$2-Pad13)") (class "Default")
      (node (ref "U$2") (pin "13") (pinfunction "13_13") (pintype "bidirectional"))
    )
    (net (code "98") (name "unconnected-(U$2-Pad14)") (class "Default")
      (node (ref "U$2") (pin "14") (pinfunction "14_14") (pintype "bidirectional"))
    )
    (net (code "99") (name "unconnected-(U$2-Pad15)") (class "Default")
      (node (ref "U$2") (pin "15") (pinfunction "15_15") (pintype "bidirectional"))
    )
    (net (code "100") (name "unconnected-(U$2-Pad16)") (class "Default")
      (node (ref "U$2") (pin "16") (pinfunction "16_16") (pintype "bidirectional"))
    )
    (net (code "101") (name "unconnected-(U$2-Pad17)") (class "Default")
      (node (ref "U$2") (pin "17") (pinfunction "17_17") (pintype "bidirectional"))
    )
    (net (code "102") (name "unconnected-(U$2-Pad18)") (class "Default")
      (node (ref "U$2") (pin "18") (pinfunction "18_18") (pintype "bidirectional"))
    )
    (net (code "103") (name "unconnected-(U$2-Pad19)") (class "Default")
      (node (ref "U$2") (pin "19") (pinfunction "19_19") (pintype "bidirectional"))
    )
    (net (code "104") (name "unconnected-(U$2-Pad20)") (class "Default")
      (node (ref "U$2") (pin "20") (pinfunction "20_20") (pintype "bidirectional"))
    )
    (net (code "105") (name "unconnected-(U$2-Pad21)") (class "Default")
      (node (ref "U$2") (pin "21") (pinfunction "21_21") (pintype "bidirectional"))
    )
    (net (code "106") (name "unconnected-(U$2-Pad22)") (class "Default")
      (node (ref "U$2") (pin "22") (pinfunction "22_22") (pintype "bidirectional"))
    )
    (net (code "107") (name "unconnected-(U$2-Pad23)") (class "Default")
      (node (ref "U$2") (pin "23") (pinfunction "23_23") (pintype "bidirectional"))
    )
    (net (code "108") (name "unconnected-(U$2-Pad24)") (class "Default")
      (node (ref "U$2") (pin "24") (pinfunction "24_24") (pintype "bidirectional"))
    )
    (net (code "109") (name "unconnected-(U$2-Pad25)") (class "Default")
      (node (ref "U$2") (pin "25") (pinfunction "25_25") (pintype "bidirectional"))
    )
    (net (code "110") (name "unconnected-(U$2-Pad26)") (class "Default")
      (node (ref "U$2") (pin "26") (pinfunction "26_26") (pintype "bidirectional"))
    )
    (net (code "111") (name "unconnected-(U$2-Pad27)") (class "Default")
      (node (ref "U$2") (pin "27") (pinfunction "27_27") (pintype "bidirectional"))
    )
    (net (code "112") (name "unconnected-(U$2-Pad28)") (class "Default")
      (node (ref "U$2") (pin "28") (pinfunction "28_28") (pintype "bidirectional"))
    )
    (net (code "113") (name "unconnected-(U$2-Pad29)") (class "Default")
      (node (ref "U$2") (pin "29") (pinfunction "29_29") (pintype "bidirectional"))
    )
    (net (code "114") (name "unconnected-(U$2-Pad30)") (class "Default")
      (node (ref "U$2") (pin "30") (pinfunction "30_30") (pintype "bidirectional"))
    )
    (net (code "115") (name "unconnected-(U$2-Pad31)") (class "Default")
      (node (ref "U$2") (pin "31") (pinfunction "31_31") (pintype "bidirectional"))
    )
    (net (code "116") (name "unconnected-(U$2-Pad32)") (class "Default")
      (node (ref "U$2") (pin "32") (pinfunction "32_32") (pintype "bidirectional"))
    )
    (net (code "117") (name "unconnected-(U$2-Pad33)") (class "Default")
      (node (ref "U$2") (pin "33") (pinfunction "33_33") (pintype "bidirectional"))
    )
    (net (code "118") (name "unconnected-(U$2-Pad34)") (class "Default")
      (node (ref "U$2") (pin "34") (pinfunction "34_34") (pintype "bidirectional"))
    )
    (net (code "119") (name "unconnected-(U$2-Pad35)") (class "Default")
      (node (ref "U$2") (pin "35") (pinfunction "35_35") (pintype "bidirectional"))
    )
    (net (code "120") (name "unconnected-(U$2-Pad36)") (class "Default")
      (node (ref "U$2") (pin "36") (pinfunction "36_36") (pintype "bidirectional"))
    )
    (net (code "121") (name "unconnected-(U$2-Pad37)") (class "Default")
      (node (ref "U$2") (pin "37") (pinfunction "37_37") (pintype "bidirectional"))
    )
    (net (code "122") (name "unconnected-(U$2-PadP$1)") (class "Default")
      (node (ref "U$2") (pin "P$1") (pinfunction "P$1_P$1") (pintype "bidirectional"))
    )
    (net (code "123") (name "unconnected-(U$2-PadP$2)") (class "Default")
      (node (ref "U$2") (pin "P$2") (pinfunction "P$2_P$2") (pintype "bidirectional"))
    )
    (net (code "124") (name "unconnected-(U$2-PadP$3)") (class "Default")
      (node (ref "U$2") (pin "P$3") (pinfunction "P$3_P$3") (pintype "bidirectional"))
    )
    (net (code "125") (name "unconnected-(U$2-PadP$4)") (class "Default")
      (node (ref "U$2") (pin "P$4") (pinfunction "P$4_P$4") (pintype "bidirectional"))
    )
    (net (code "126") (name "unconnected-(U1-A0-Pad7)") (class "Default")
      (node (ref "U1") (pin "7") (pinfunction "A0_7") (pintype "input"))
    )
    (net (code "127") (name "unconnected-(U1-A1-Pad6)") (class "Default")
      (node (ref "U1") (pin "6") (pinfunction "A1_6") (pintype "input"))
    )
    (net (code "128") (name "unconnected-(U1-A2-Pad5)") (class "Default")
      (node (ref "U1") (pin "5") (pinfunction "A2_5") (pintype "input"))
    )
    (net (code "129") (name "unconnected-(U3-GPIO_2-Pad16)") (class "Default")
      (node (ref "U3") (pin "16") (pinfunction "GPIO_2_16") (pintype "bidirectional"))
    )
    (net (code "130") (name "unconnected-(U4-DIO0-Pad14)") (class "Default")
      (node (ref "U4") (pin "14") (pinfunction "DIO0_14") (pintype "bidirectional"))
    )
    (net (code "131") (name "unconnected-(U4-DIO2-Pad16)") (class "Default")
      (node (ref "U4") (pin "16") (pinfunction "DIO2_16") (pintype "bidirectional"))
    )
    (net (code "132") (name "unconnected-(U4-DIO3-Pad11)") (class "Default")
      (node (ref "U4") (pin "11") (pinfunction "DIO3_11") (pintype "bidirectional"))
    )
    (net (code "133") (name "unconnected-(U4-DIO4-Pad12)") (class "Default")
      (node (ref "U4") (pin "12") (pinfunction "DIO4_12") (pintype "bidirectional"))
    )
    (net (code "134") (name "unconnected-(U4-DIO5-Pad7)") (class "Default")
      (node (ref "U4") (pin "7") (pinfunction "DIO5_7") (pintype "bidirectional"))
    )
    (net (code "135") (name "unconnected-(U5-Pad1)") (class "Default")
      (node (ref "U5") (pin "1") (pinfunction "1_1") (pintype "passive"))
    )
    (net (code "136") (name "unconnected-(X1-P$1-Pad1)") (class "Default")
      (node (ref "X1") (pin "1") (pinfunction "P$1_1") (pintype "bidirectional"))
    )
    (net (code "137") (name "unconnected-(X1-P$4-Pad4)") (class "Default")
      (node (ref "X1") (pin "4") (pinfunction "P$4_4") (pintype "bidirectional"))
    )
    (net (code "138") (name "unconnected-(X1-P$6-Pad6)") (class "Default")
      (node (ref "X1") (pin "6") (pinfunction "P$6_6") (pintype "bidirectional"))
    )
    (net (code "139") (name "unconnected-(X1-P$7-Pad7)") (class "Default")
      (node (ref "X1") (pin "7") (pinfunction "P$7_7") (pintype "bidirectional"))
    )
    (net (code "140") (name "unconnected-(X1-P$9-Pad9)") (class "Default")
      (node (ref "X1") (pin "9") (pinfunction "P$9_9") (pintype "bidirectional"))
    )
    (net (code "141") (name "unconnected-(X1-P$12-Pad12)") (class "Default")
      (node (ref "X1") (pin "12") (pinfunction "P$12_12") (pintype "bidirectional"))
    )
    (net (code "142") (name "unconnected-(X1-P$14-Pad14)") (class "Default")
      (node (ref "X1") (pin "14") (pinfunction "P$14_14") (pintype "bidirectional"))
    )
    (net (code "143") (name "unconnected-(X1-P$17-Pad17)") (class "Default")
      (node (ref "X1") (pin "17") (pinfunction "P$17_17") (pintype "bidirectional"))
    )
    (net (code "144") (name "unconnected-(X1-P$20-Pad20)") (class "Default")
      (node (ref "X1") (pin "20") (pinfunction "P$20_20") (pintype "bidirectional"))
    )
    (net (code "145") (name "unconnected-(X1-P$25-Pad25)") (class "Default")
      (node (ref "X1") (pin "25") (pinfunction "P$25_25") (pintype "bidirectional"))
    )
    (net (code "146") (name "unconnected-(X1-P$27-Pad27)") (class "Default")
      (node (ref "X1") (pin "27") (pinfunction "P$27_27") (pintype "bidirectional"))
    )
    (net (code "147") (name "unconnected-(X1-P$28-Pad28)") (class "Default")
      (node (ref "X1") (pin "28") (pinfunction "P$28_28") (pintype "bidirectional"))
    )
    (net (code "148") (name "unconnected-(X1-P$29-Pad29)") (class "Default")
      (node (ref "X1") (pin "29") (pinfunction "P$29_29") (pintype "bidirectional"))
    )
    (net (code "149") (name "unconnected-(X1-P$30-Pad30)") (class "Default")
      (node (ref "X1") (pin "30") (pinfunction "P$30_30") (pintype "bidirectional"))
    )
    (net (code "150") (name "unconnected-(X1-P$31-Pad31)") (class "Default")
      (node (ref "X1") (pin "31") (pinfunction "P$31_31") (pintype "bidirectional"))
    )
    (net (code "151") (name "unconnected-(X1-P$32-Pad32)") (class "Default")
      (node (ref "X1") (pin "32") (pinfunction "P$32_32") (pintype "bidirectional"))
    )
    (net (code "152") (name "unconnected-(X1-P$33-Pad33)") (class "Default")
      (node (ref "X1") (pin "33") (pinfunction "P$33_33") (pintype "bidirectional"))
    )
    (net (code "153") (name "unconnected-(X1-P$34-Pad34)") (class "Default")
      (node (ref "X1") (pin "34") (pinfunction "P$34_34") (pintype "bidirectional"))
    )
    (net (code "154") (name "unconnected-(X1-P$35-Pad35)") (class "Default")
      (node (ref "X1") (pin "35") (pinfunction "P$35_35") (pintype "bidirectional"))
    )
    (net (code "155") (name "unconnected-(X1-P$36-Pad36)") (class "Default")
      (node (ref "X1") (pin "36") (pinfunction "P$36_36") (pintype "bidirectional"))
    )
    (net (code "156") (name "unconnected-(X1-P$37-Pad37)") (class "Default")
      (node (ref "X1") (pin "37") (pinfunction "P$37_37") (pintype "bidirectional"))
    )
    (net (code "157") (name "unconnected-(X1-P$38-Pad38)") (class "Default")
      (node (ref "X1") (pin "38") (pinfunction "P$38_38") (pintype "bidirectional"))
    )
    (net (code "158") (name "unconnected-(X1-P$40-Pad40)") (class "Default")
      (node (ref "X1") (pin "40") (pinfunction "P$40_40") (pintype "bidirectional"))
    )
    (net (code "159") (name "unconnected-(X2-Pad1)") (class "Default")
      (node (ref "X2") (pin "1") (pinfunction "1_1") (pintype "passive"))
    )
    (net (code "160") (name "unconnected-(X2AA-1-Pad33)") (class "Default")
      (node (ref "X2") (pin "33") (pinfunction "1_33") (pintype "passive"))
    )
    (net (code "161") (name "unconnected-(X2AB-1-Pad34)") (class "Default")
      (node (ref "X2") (pin "34") (pinfunction "1_34") (pintype "passive"))
    )
    (net (code "162") (name "unconnected-(X2AC-1-Pad35)") (class "Default")
      (node (ref "X2") (pin "35") (pinfunction "1_35") (pintype "passive"))
    )
    (net (code "163") (name "unconnected-(X2AD-1-Pad36)") (class "Default")
      (node (ref "X2") (pin "36") (pinfunction "1_36") (pintype "passive"))
    )
    (net (code "164") (name "unconnected-(X2AE-1-Pad37)") (class "Default")
      (node (ref "X2") (pin "37") (pinfunction "1_37") (pintype "passive"))
    )
    (net (code "165") (name "unconnected-(X2AF-1-Pad38)") (class "Default")
      (node (ref "X2") (pin "38") (pinfunction "1_38") (pintype "passive"))
    )
    (net (code "166") (name "unconnected-(X2AG-1-Pad39)") (class "Default")
      (node (ref "X2") (pin "39") (pinfunction "1_39") (pintype "passive"))
    )
    (net (code "167") (name "unconnected-(X2AH-1-Pad4)") (class "Default")
      (node (ref "X2") (pin "4") (pinfunction "1_4") (pintype "passive"))
    )
    (net (code "168") (name "unconnected-(X2AI-1-Pad40)") (class "Default")
      (node (ref "X2") (pin "40") (pinfunction "1_40") (pintype "passive"))
    )
    (net (code "169") (name "unconnected-(X2AJ-1-Pad5)") (class "Default")
      (node (ref "X2") (pin "5") (pinfunction "1_5") (pintype "passive"))
    )
    (net (code "170") (name "unconnected-(X2AK-1-Pad6)") (class "Default")
      (node (ref "X2") (pin "6") (pinfunction "1_6") (pintype "passive"))
    )
    (net (code "171") (name "unconnected-(X2AL-1-Pad7)") (class "Default")
      (node (ref "X2") (pin "7") (pinfunction "1_7") (pintype "passive"))
    )
    (net (code "172") (name "unconnected-(X2AM-1-Pad8)") (class "Default")
      (node (ref "X2") (pin "8") (pinfunction "1_8") (pintype "passive"))
    )
    (net (code "173") (name "unconnected-(X2AN-1-Pad9)") (class "Default")
      (node (ref "X2") (pin "9") (pinfunction "1_9") (pintype "passive"))
    )
    (net (code "174") (name "unconnected-(X2B-1-Pad10)") (class "Default")
      (node (ref "X2") (pin "10") (pinfunction "1_10") (pintype "passive"))
    )
    (net (code "175") (name "unconnected-(X2C-1-Pad11)") (class "Default")
      (node (ref "X2") (pin "11") (pinfunction "1_11") (pintype "passive"))
    )
    (net (code "176") (name "unconnected-(X2D-1-Pad12)") (class "Default")
      (node (ref "X2") (pin "12") (pinfunction "1_12") (pintype "passive"))
    )
    (net (code "177") (name "unconnected-(X2E-1-Pad13)") (class "Default")
      (node (ref "X2") (pin "13") (pinfunction "1_13") (pintype "passive"))
    )
    (net (code "178") (name "unconnected-(X2F-1-Pad14)") (class "Default")
      (node (ref "X2") (pin "14") (pinfunction "1_14") (pintype "passive"))
    )
    (net (code "179") (name "unconnected-(X2G-1-Pad15)") (class "Default")
      (node (ref "X2") (pin "15") (pinfunction "1_15") (pintype "passive"))
    )
    (net (code "180") (name "unconnected-(X2H-1-Pad16)") (class "Default")
      (node (ref "X2") (pin "16") (pinfunction "1_16") (pintype "passive"))
    )
    (net (code "181") (name "unconnected-(X2I-1-Pad17)") (class "Default")
      (node (ref "X2") (pin "17") (pinfunction "1_17") (pintype "passive"))
    )
    (net (code "182") (name "unconnected-(X2J-1-Pad18)") (class "Default")
      (node (ref "X2") (pin "18") (pinfunction "1_18") (pintype "passive"))
    )
    (net (code "183") (name "unconnected-(X2K-1-Pad19)") (class "Default")
      (node (ref "X2") (pin "19") (pinfunction "1_19") (pintype "passive"))
    )
    (net (code "184") (name "unconnected-(X2L-1-Pad2)") (class "Default")
      (node (ref "X2") (pin "2") (pinfunction "1_2") (pintype "passive"))
    )
    (net (code "185") (name "unconnected-(X2M-1-Pad20)") (class "Default")
      (node (ref "X2") (pin "20") (pinfunction "1_20") (pintype "passive"))
    )
    (net (code "186") (name "unconnected-(X2N-1-Pad21)") (class "Default")
      (node (ref "X2") (pin "21") (pinfunction "1_21") (pintype "passive"))
    )
    (net (code "187") (name "unconnected-(X2O-1-Pad22)") (class "Default")
      (node (ref "X2") (pin "22") (pinfunction "1_22") (pintype "passive"))
    )
    (net (code "188") (name "unconnected-(X2P-1-Pad23)") (class "Default")
      (node (ref "X2") (pin "23") (pinfunction "1_23") (pintype "passive"))
    )
    (net (code "189") (name "unconnected-(X2Q-1-Pad24)") (class "Default")
      (node (ref "X2") (pin "24") (pinfunction "1_24") (pintype "passive"))
    )
    (net (code "190") (name "unconnected-(X2R-1-Pad25)") (class "Default")
      (node (ref "X2") (pin "25") (pinfunction "1_25") (pintype "passive"))
    )
    (net (code "191") (name "unconnected-(X2S-1-Pad26)") (class "Default")
      (node (ref "X2") (pin "26") (pinfunction "1_26") (pintype "passive"))
    )
    (net (code "192") (name "unconnected-(X2T-1-Pad27)") (class "Default")
      (node (ref "X2") (pin "27") (pinfunction "1_27") (pintype "passive"))
    )
    (net (code "193") (name "unconnected-(X2U-1-Pad28)") (class "Default")
      (node (ref "X2") (pin "28") (pinfunction "1_28") (pintype "passive"))
    )
    (net (code "194") (name "unconnected-(X2V-1-Pad29)") (class "Default")
      (node (ref "X2") (pin "29") (pinfunction "1_29") (pintype "passive"))
    )
    (net (code "195") (name "unconnected-(X2W-1-Pad3)") (class "Default")
      (node (ref "X2") (pin "3") (pinfunction "1_3") (pintype "passive"))
    )
    (net (code "196") (name "unconnected-(X2X-1-Pad30)") (class "Default")
      (node (ref "X2") (pin "30") (pinfunction "1_30") (pintype "passive"))
    )
    (net (code "197") (name "unconnected-(X2Y-1-Pad31)") (class "Default")
      (node (ref "X2") (pin "31") (pinfunction "1_31") (pintype "passive"))
    )
    (net (code "198") (name "unconnected-(X2Z-1-Pad32)") (class "Default")
      (node (ref "X2") (pin "32") (pinfunction "1_32") (pintype "passive"))
    )
  )
)
